# project_step_down.net
KiCad netlist of a schematic drawn in EAGLE
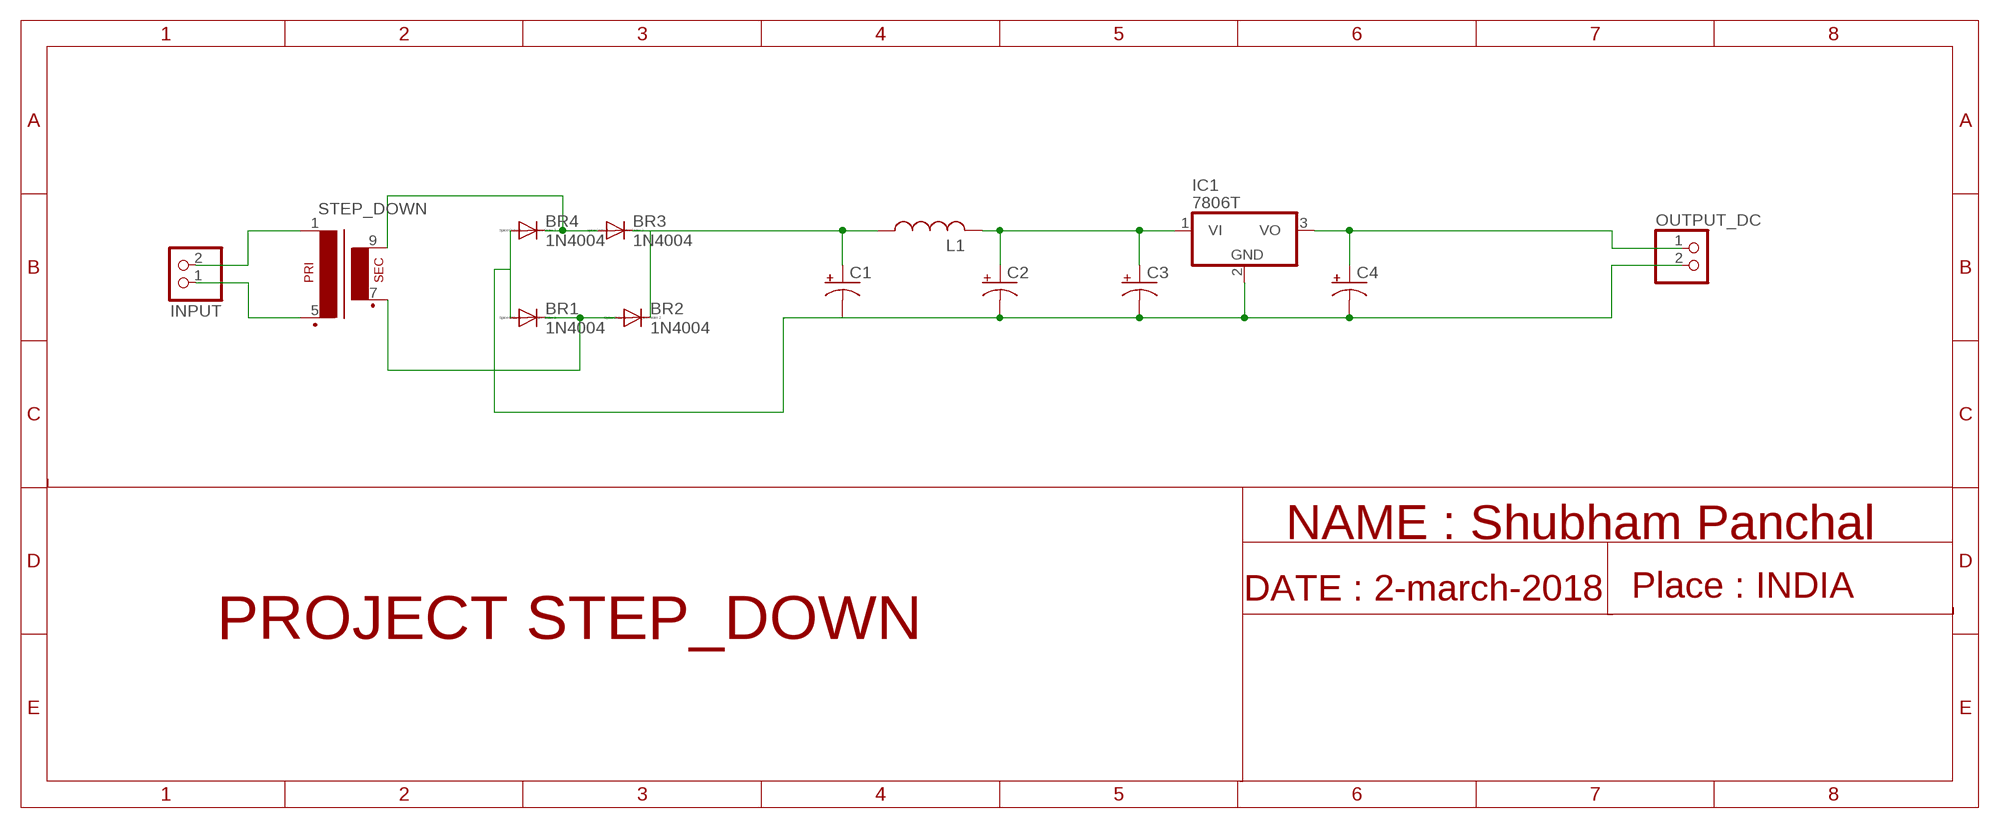
[diagram p0: schematic, sheet 1]

(export (version "E")
  (design (tool "Eeschema 10.0.6"))
  (components
    (comp (ref "BR1")
      (value "1N4004")
      (footprint "eagle-import:DO41-10")
      (libsource (lib "eagle-import") (part "1N4004"))
    )
    (comp (ref "BR2")
      (value "1N4004")
      (footprint "eagle-import:DO41-10")
      (libsource (lib "eagle-import") (part "1N4004"))
    )
    (comp (ref "BR3")
      (value "1N4004")
      (footprint "eagle-import:DO41-10")
      (libsource (lib "eagle-import") (part "1N4004"))
    )
    (comp (ref "BR4")
      (value "1N4004")
      (footprint "eagle-import:DO41-10")
      (libsource (lib "eagle-import") (part "1N4004"))
    )
    (comp (ref "C1")
      (value "CPOL-USE2.5-7")
      (footprint "eagle-import:E2,5-7")
      (libsource (lib "eagle-import") (part "CPOL-USE2.5-7"))
    )
    (comp (ref "C2")
      (value "CPOL-USE2.5-7")
      (footprint "eagle-import:E2,5-7")
      (libsource (lib "eagle-import") (part "CPOL-USE2.5-7"))
    )
    (comp (ref "C3")
      (value "CPOL-USE2.5-7")
      (footprint "eagle-import:E2,5-7")
      (libsource (lib "eagle-import") (part "CPOL-USE2.5-7"))
    )
    (comp (ref "C4")
      (value "CPOL-USE2.5-7")
      (footprint "eagle-import:E2,5-7")
      (libsource (lib "eagle-import") (part "CPOL-USE2.5-7"))
    )
    (comp (ref "IC1")
      (value "7806T")
      (footprint "eagle-import:TO220H")
      (libsource (lib "eagle-import") (part "78T06"))
    )
    (comp (ref "INPUT")
      (value "PINHD-1X2")
      (footprint "eagle-import:1X02")
      (libsource (lib "eagle-import") (part "PINHD-1X2"))
    )
    (comp (ref "L1")
      (value "L-US0204/7")
      (footprint "eagle-import:0204_7")
      (libsource (lib "eagle-import") (part "L-US0204/7"))
    )
    (comp (ref "OUTPUT_DC")
      (value "PINHD-1X2")
      (footprint "eagle-import:1X02")
      (libsource (lib "eagle-import") (part "PINHD-1X2"))
    )
    (comp (ref "STEP_DOWN")
      (value "EI30-1")
      (footprint "eagle-import:EI30-1")
      (libsource (lib "eagle-import") (part "EI30-1"))
    )
  )
  (nets
    (net (code "1") (name "/GND") (class "Default")
      (node (ref "C1") (pin "-") (pinfunction "-_-") (pintype "passive"))
      (node (ref "C2") (pin "-") (pinfunction "-_-") (pintype "passive"))
      (node (ref "C3") (pin "-") (pinfunction "-_-") (pintype "passive"))
      (node (ref "C4") (pin "-") (pinfunction "-_-") (pintype "passive"))
      (node (ref "IC1") (pin "2") (pinfunction "GND_2") (pintype "passive"))
      (node (ref "OUTPUT_DC") (pin "2") (pinfunction "2_2") (pintype "passive"))
    )
    (net (code "2") (name "Net-(BR1-PadA)") (class "Default")
      (node (ref "BR1") (pin "A") (pinfunction "A_A") (pintype "passive"))
      (node (ref "BR4") (pin "A") (pinfunction "A_A") (pintype "passive"))
    )
    (net (code "3") (name "Net-(BR2-PadC)") (class "Default")
      (node (ref "BR2") (pin "C") (pinfunction "C_C") (pintype "passive"))
      (node (ref "BR3") (pin "C") (pinfunction "C_C") (pintype "passive"))
      (node (ref "C1") (pin "+") (pinfunction "+_+") (pintype "passive"))
      (node (ref "L1") (pin "1") (pinfunction "1_1") (pintype "passive"))
    )
    (net (code "4") (name "Net-(IC1-VI)") (class "Default")
      (node (ref "C2") (pin "+") (pinfunction "+_+") (pintype "passive"))
      (node (ref "C3") (pin "+") (pinfunction "+_+") (pintype "passive"))
      (node (ref "IC1") (pin "1") (pinfunction "VI_1") (pintype "input"))
      (node (ref "L1") (pin "2") (pinfunction "2_2") (pintype "passive"))
    )
    (net (code "5") (name "Net-(IC1-VO)") (class "Default")
      (node (ref "C4") (pin "+") (pinfunction "+_+") (pintype "passive"))
      (node (ref "IC1") (pin "3") (pinfunction "VO_3") (pintype "passive"))
      (node (ref "OUTPUT_DC") (pin "1") (pinfunction "1_1") (pintype "passive"))
    )
    (net (code "6") (name "Net-(STEP_DOWN-P1)") (class "Default")
      (node (ref "INPUT") (pin "2") (pinfunction "2_2") (pintype "passive"))
      (node (ref "STEP_DOWN") (pin "1") (pinfunction "P1_1") (pintype "passive"))
    )
    (net (code "7") (name "Net-(STEP_DOWN-P2)") (class "Default")
      (node (ref "INPUT") (pin "1") (pinfunction "1_1") (pintype "passive"))
      (node (ref "STEP_DOWN") (pin "5") (pinfunction "P2_5") (pintype "passive"))
    )
    (net (code "8") (name "Net-(STEP_DOWN-S3)") (class "Default")
      (node (ref "BR1") (pin "C") (pinfunction "C_C") (pintype "passive"))
      (node (ref "BR2") (pin "A") (pinfunction "A_A") (pintype "passive"))
      (node (ref "STEP_DOWN") (pin "7") (pinfunction "S3_7") (pintype "passive"))
    )
    (net (code "9") (name "Net-(STEP_DOWN-S4)") (class "Default")
      (node (ref "BR3") (pin "A") (pinfunction "A_A") (pintype "passive"))
      (node (ref "BR4") (pin "C") (pinfunction "C_C") (pintype "passive"))
      (node (ref "STEP_DOWN") (pin "9") (pinfunction "S4_9") (pintype "passive"))
    )
  )
)
